# untitled.net
KiCad netlist of a schematic drawn in EAGLE
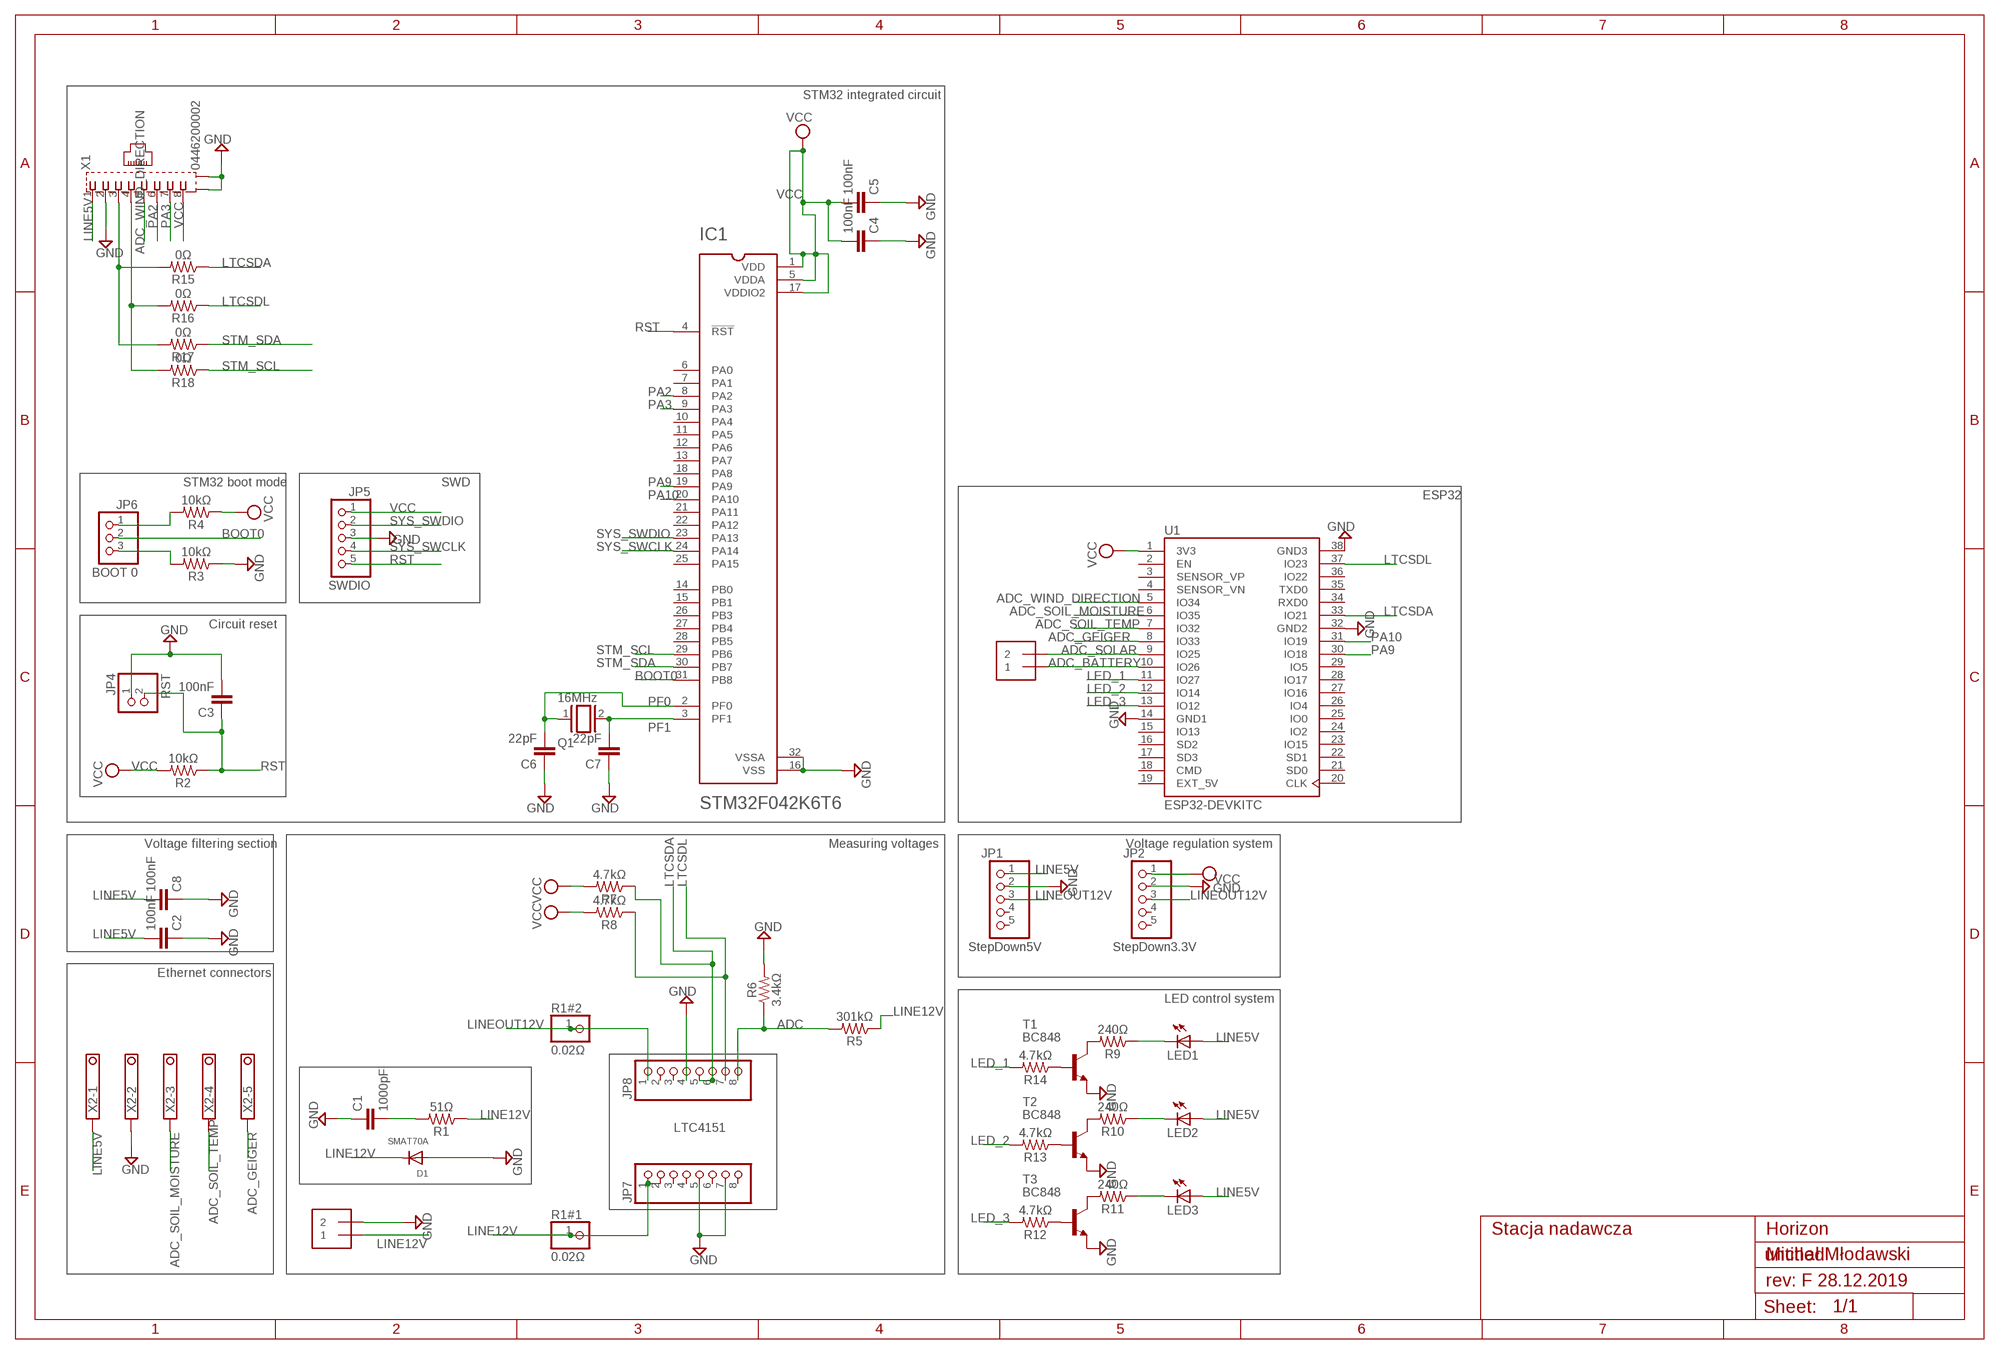
[diagram p0: schematic, sheet 1]

(export (version "E")
  (design (tool "Eeschema 10.0.6"))
  (components
    (comp (ref "C1")
      (value "1000pF")
      (footprint "eagle-import:1206")
      (libsource (lib "eagle-import") (part "10UF-1206-6.3V-20%"))
    )
    (comp (ref "C2")
      (value "100nF")
      (footprint "eagle-import:1206")
      (libsource (lib "eagle-import") (part "10UF-1206-6.3V-20%"))
    )
    (comp (ref "C3")
      (value "100nF")
      (footprint "eagle-import:1206")
      (libsource (lib "eagle-import") (part "10UF-1206-6.3V-20%"))
    )
    (comp (ref "C4")
      (value "100nF")
      (footprint "eagle-import:1206")
      (libsource (lib "eagle-import") (part "10UF-1206-6.3V-20%"))
    )
    (comp (ref "C5")
      (value "100nF")
      (footprint "eagle-import:1206")
      (libsource (lib "eagle-import") (part "10UF-1206-6.3V-20%"))
    )
    (comp (ref "C6")
      (value "22pF")
      (footprint "eagle-import:1206")
      (libsource (lib "eagle-import") (part "10UF-1206-6.3V-20%"))
    )
    (comp (ref "C7")
      (value "22pF")
      (footprint "eagle-import:1206")
      (libsource (lib "eagle-import") (part "10UF-1206-6.3V-20%"))
    )
    (comp (ref "C8")
      (value "100nF")
      (footprint "eagle-import:1206")
      (libsource (lib "eagle-import") (part "10UF-1206-6.3V-20%"))
    )
    (comp (ref "D1")
      (value "SMAT70A")
      (footprint "eagle-import:SMADIODE")
      (libsource (lib "eagle-import") (part "DIODESMA"))
    )
    (comp (ref "IC1")
      (value "STM32F042K6T6")
      (footprint "eagle-import:QFP80P900X900X160-32N")
      (fields (field (name "MF") "STMicroelectronics"))
      (libsource (lib "eagle-import") (part "STM32F042K6T6"))
    )
    (comp (ref "J1")
      (value "1X2-3.5MM")
      (footprint "eagle-import:1X2-3.5MM")
      (libsource (lib "eagle-import") (part "1X2-3.5MM"))
    )
    (comp (ref "J2")
      (value "1X2-3.5MM")
      (footprint "eagle-import:1X2-3.5MM")
      (libsource (lib "eagle-import") (part "1X2-3.5MM"))
    )
    (comp (ref "JP1")
      (value "StepDown5V")
      (footprint "eagle-import:1X05")
      (libsource (lib "eagle-import") (part "PINHD-1X5"))
    )
    (comp (ref "JP2")
      (value "StepDown3.3V")
      (footprint "eagle-import:1X05")
      (libsource (lib "eagle-import") (part "PINHD-1X5"))
    )
    (comp (ref "JP4")
      (value "RST")
      (footprint "eagle-import:1X02")
      (libsource (lib "eagle-import") (part "PINHD-1X2"))
    )
    (comp (ref "JP5")
      (value "SWDIO")
      (footprint "eagle-import:1X05")
      (libsource (lib "eagle-import") (part "PINHD-1X5"))
    )
    (comp (ref "JP6")
      (value "BOOT 0")
      (footprint "eagle-import:1X03")
      (libsource (lib "eagle-import") (part "PINHD-1X3"))
    )
    (comp (ref "JP7")
      (value "PINHD-1X8")
      (footprint "eagle-import:1X08")
      (libsource (lib "eagle-import") (part "PINHD-1X8"))
    )
    (comp (ref "JP8")
      (value "PINHD-1X8")
      (footprint "eagle-import:1X08")
      (libsource (lib "eagle-import") (part "PINHD-1X8"))
    )
    (comp (ref "LED1")
      (value "LED5MM")
      (footprint "eagle-import:LED5MM")
      (libsource (lib "eagle-import") (part "LED5MM"))
    )
    (comp (ref "LED2")
      (value "LED5MM")
      (footprint "eagle-import:LED5MM")
      (libsource (lib "eagle-import") (part "LED5MM"))
    )
    (comp (ref "LED3")
      (value "LED5MM")
      (footprint "eagle-import:LED5MM")
      (libsource (lib "eagle-import") (part "LED5MM"))
    )
    (comp (ref "Q1")
      (value "16MHz")
      (footprint "eagle-import:QS")
      (libsource (lib "eagle-import") (part "XTAL/S"))
    )
    (comp (ref "R1")
      (value "51Ω")
      (footprint "eagle-import:1206")
      (libsource (lib "eagle-import") (part "RESISTOR1206"))
    )
    (comp (ref "R1#1")
      (value "0.02Ω")
      (footprint "eagle-import:1X01")
      (libsource (lib "eagle-import") (part "PINHD-1X1"))
    )
    (comp (ref "R1#2")
      (value "0.02Ω")
      (footprint "eagle-import:1X01")
      (libsource (lib "eagle-import") (part "PINHD-1X1"))
    )
    (comp (ref "R2")
      (value "10kΩ")
      (footprint "eagle-import:1206")
      (libsource (lib "eagle-import") (part "RESISTOR1206"))
    )
    (comp (ref "R3")
      (value "10kΩ")
      (footprint "eagle-import:1206")
      (libsource (lib "eagle-import") (part "RESISTOR1206"))
    )
    (comp (ref "R4")
      (value "10kΩ")
      (footprint "eagle-import:1206")
      (libsource (lib "eagle-import") (part "RESISTOR1206"))
    )
    (comp (ref "R5")
      (value "301kΩ")
      (footprint "eagle-import:1206")
      (libsource (lib "eagle-import") (part "RESISTOR1206"))
    )
    (comp (ref "R6")
      (value "3.4kΩ")
      (footprint "eagle-import:1206")
      (libsource (lib "eagle-import") (part "RESISTOR1206"))
    )
    (comp (ref "R7")
      (value "4.7kΩ")
      (footprint "eagle-import:1206")
      (libsource (lib "eagle-import") (part "RESISTOR1206"))
    )
    (comp (ref "R8")
      (value "4.7kΩ")
      (footprint "eagle-import:1206")
      (libsource (lib "eagle-import") (part "RESISTOR1206"))
    )
    (comp (ref "R9")
      (value "240Ω")
      (footprint "eagle-import:1206")
      (libsource (lib "eagle-import") (part "RESISTOR1206"))
    )
    (comp (ref "R10")
      (value "240Ω")
      (footprint "eagle-import:1206")
      (libsource (lib "eagle-import") (part "RESISTOR1206"))
    )
    (comp (ref "R11")
      (value "240Ω")
      (footprint "eagle-import:1206")
      (libsource (lib "eagle-import") (part "RESISTOR1206"))
    )
    (comp (ref "R12")
      (value "4.7kΩ")
      (footprint "eagle-import:1206")
      (libsource (lib "eagle-import") (part "RESISTOR1206"))
    )
    (comp (ref "R13")
      (value "4.7kΩ")
      (footprint "eagle-import:1206")
      (libsource (lib "eagle-import") (part "RESISTOR1206"))
    )
    (comp (ref "R14")
      (value "4.7kΩ")
      (footprint "eagle-import:1206")
      (libsource (lib "eagle-import") (part "RESISTOR1206"))
    )
    (comp (ref "R15")
      (value "0Ω")
      (footprint "eagle-import:1206")
      (libsource (lib "eagle-import") (part "RESISTOR1206"))
    )
    (comp (ref "R16")
      (value "0Ω")
      (footprint "eagle-import:1206")
      (libsource (lib "eagle-import") (part "RESISTOR1206"))
    )
    (comp (ref "R17")
      (value "0Ω")
      (footprint "eagle-import:1206")
      (libsource (lib "eagle-import") (part "RESISTOR1206"))
    )
    (comp (ref "R18")
      (value "0Ω")
      (footprint "eagle-import:1206")
      (libsource (lib "eagle-import") (part "RESISTOR1206"))
    )
    (comp (ref "T1")
      (value "BC848")
      (footprint "eagle-import:SOT23")
      (libsource (lib "eagle-import") (part "BC848"))
    )
    (comp (ref "T2")
      (value "BC848")
      (footprint "eagle-import:SOT23")
      (libsource (lib "eagle-import") (part "BC848"))
    )
    (comp (ref "T3")
      (value "BC848")
      (footprint "eagle-import:SOT23")
      (libsource (lib "eagle-import") (part "BC848"))
    )
    (comp (ref "U1")
      (value "ESP32-DEVKITC")
      (footprint "eagle-import:MODULE_ESP32-DEVKITC")
      (fields (field (name "MF") "Espressif Systems") (field (name "MP") "ESP32-DEVKITC-32D-F"))
      (libsource (lib "eagle-import") (part "ESP32-DEVKITC"))
    )
    (comp (ref "X1")
      (value "0446200002")
      (footprint "eagle-import:0446200002")
      (fields (field (name "MF") "MOLEX"))
      (libsource (lib "eagle-import") (part "0446200002"))
    )
    (comp (ref "X2")
      (value "TERMINAL-BLOCK-3.5MM-5-PIN-LONG-PAD")
      (footprint "eagle-import:TERMINAL-BLOCK-5-PIN-3.5MM-LONG-PAD")
      (libsource (lib "eagle-import") (part "TERMINAL-BLOCK-3.5MM-5-PIN-LONG-PAD"))
    )
  )
  (nets
    (net (code "1") (name "/ADC") (class "Default")
      (node (ref "JP8") (pin "8") (pinfunction "8_8") (pintype "passive"))
      (node (ref "R5") (pin "2") (pinfunction "2_2") (pintype "passive"))
      (node (ref "R6") (pin "1") (pinfunction "1_1") (pintype "passive"))
    )
    (net (code "2") (name "/ADC_BATTERY") (class "Default")
      (node (ref "J1") (pin "1") (pinfunction "1_1") (pintype "passive"))
      (node (ref "U1") (pin "10") (pinfunction "IO26_10") (pintype "bidirectional"))
    )
    (net (code "3") (name "/ADC_GEIGER") (class "Default")
      (node (ref "U1") (pin "8") (pinfunction "IO33_8") (pintype "bidirectional"))
      (node (ref "X2") (pin "5") (pinfunction "K_5") (pintype "passive"))
    )
    (net (code "4") (name "/ADC_SOIL_MOISTURE") (class "Default")
      (node (ref "U1") (pin "6") (pinfunction "IO35_6") (pintype "bidirectional"))
      (node (ref "X2") (pin "3") (pinfunction "K_3") (pintype "passive"))
    )
    (net (code "5") (name "/ADC_SOIL_TEMP") (class "Default")
      (node (ref "U1") (pin "7") (pinfunction "IO32_7") (pintype "bidirectional"))
      (node (ref "X2") (pin "4") (pinfunction "K_4") (pintype "passive"))
    )
    (net (code "6") (name "/ADC_SOLAR") (class "Default")
      (node (ref "J1") (pin "2") (pinfunction "2_2") (pintype "passive"))
      (node (ref "U1") (pin "9") (pinfunction "IO25_9") (pintype "bidirectional"))
    )
    (net (code "7") (name "/ADC_WIND_DIRECTION") (class "Default")
      (node (ref "U1") (pin "5") (pinfunction "IO34_5") (pintype "bidirectional"))
      (node (ref "X1") (pin "5") (pinfunction "5_5") (pintype "passive"))
    )
    (net (code "8") (name "/BOOT0") (class "Default")
      (node (ref "IC1") (pin "31") (pinfunction "PB8_31") (pintype "bidirectional"))
      (node (ref "JP6") (pin "2") (pinfunction "2_2") (pintype "passive"))
    )
    (net (code "9") (name "/EXT_5V") (class "Default")
      (node (ref "U1") (pin "19") (pinfunction "EXT_5V_19") (pintype "power_in"))
    )
    (net (code "10") (name "/LED_1") (class "Default")
      (node (ref "R14") (pin "2") (pinfunction "2_2") (pintype "passive"))
      (node (ref "U1") (pin "11") (pinfunction "IO27_11") (pintype "bidirectional"))
    )
    (net (code "11") (name "/LED_2") (class "Default")
      (node (ref "R13") (pin "2") (pinfunction "2_2") (pintype "passive"))
      (node (ref "U1") (pin "12") (pinfunction "IO14_12") (pintype "bidirectional"))
    )
    (net (code "12") (name "/LED_3") (class "Default")
      (node (ref "R12") (pin "2") (pinfunction "2_2") (pintype "passive"))
      (node (ref "U1") (pin "13") (pinfunction "IO12_13") (pintype "bidirectional"))
    )
    (net (code "13") (name "/LINE5V") (class "Default")
      (node (ref "C2") (pin "2") (pinfunction "2_2") (pintype "passive"))
      (node (ref "C8") (pin "2") (pinfunction "2_2") (pintype "passive"))
      (node (ref "JP1") (pin "1") (pinfunction "1_1") (pintype "passive"))
      (node (ref "LED1") (pin "A") (pinfunction "A_A") (pintype "passive"))
      (node (ref "LED2") (pin "A") (pinfunction "A_A") (pintype "passive"))
      (node (ref "LED3") (pin "A") (pinfunction "A_A") (pintype "passive"))
      (node (ref "X1") (pin "1") (pinfunction "1_1") (pintype "passive"))
      (node (ref "X2") (pin "1") (pinfunction "K_1") (pintype "passive"))
    )
    (net (code "14") (name "/LINE12V") (class "Default")
      (node (ref "D1") (pin "C") (pinfunction "C_C") (pintype "passive"))
      (node (ref "J2") (pin "1") (pinfunction "1_1") (pintype "passive"))
      (node (ref "JP7") (pin "1") (pinfunction "1_1") (pintype "passive"))
      (node (ref "JP7") (pin "2") (pinfunction "2_2") (pintype "passive"))
      (node (ref "R1") (pin "1") (pinfunction "1_1") (pintype "passive"))
      (node (ref "R1#1") (pin "1") (pinfunction "1_1") (pintype "passive"))
      (node (ref "R5") (pin "1") (pinfunction "1_1") (pintype "passive"))
    )
    (net (code "15") (name "/LINEOUT12V") (class "Default")
      (node (ref "JP1") (pin "3") (pinfunction "3_3") (pintype "passive"))
      (node (ref "JP2") (pin "3") (pinfunction "3_3") (pintype "passive"))
      (node (ref "JP8") (pin "1") (pinfunction "1_1") (pintype "passive"))
      (node (ref "R1#2") (pin "1") (pinfunction "1_1") (pintype "passive"))
    )
    (net (code "16") (name "/LTCSDA") (class "Default")
      (node (ref "JP8") (pin "5") (pinfunction "5_5") (pintype "passive"))
      (node (ref "JP8") (pin "6") (pinfunction "6_6") (pintype "passive"))
      (node (ref "R15") (pin "1") (pinfunction "1_1") (pintype "passive"))
      (node (ref "R7") (pin "1") (pinfunction "1_1") (pintype "passive"))
      (node (ref "U1") (pin "33") (pinfunction "IO21_33") (pintype "bidirectional"))
    )
    (net (code "17") (name "/LTCSDL") (class "Default")
      (node (ref "JP8") (pin "7") (pinfunction "7_7") (pintype "passive"))
      (node (ref "R16") (pin "1") (pinfunction "1_1") (pintype "passive"))
      (node (ref "R8") (pin "1") (pinfunction "1_1") (pintype "passive"))
      (node (ref "U1") (pin "37") (pinfunction "IO23_37") (pintype "bidirectional"))
    )
    (net (code "18") (name "/PA2") (class "Default")
      (node (ref "IC1") (pin "8") (pinfunction "PA2_8") (pintype "bidirectional"))
      (node (ref "X1") (pin "6") (pinfunction "6_6") (pintype "passive"))
    )
    (net (code "19") (name "/PA3") (class "Default")
      (node (ref "IC1") (pin "9") (pinfunction "PA3_9") (pintype "bidirectional"))
      (node (ref "X1") (pin "7") (pinfunction "7_7") (pintype "passive"))
    )
    (net (code "20") (name "/PA9") (class "Default")
      (node (ref "IC1") (pin "19") (pinfunction "PA9_19") (pintype "bidirectional"))
      (node (ref "U1") (pin "30") (pinfunction "IO18_30") (pintype "bidirectional"))
    )
    (net (code "21") (name "/PA10") (class "Default")
      (node (ref "IC1") (pin "20") (pinfunction "PA10_20") (pintype "bidirectional"))
      (node (ref "U1") (pin "31") (pinfunction "IO19_31") (pintype "bidirectional"))
    )
    (net (code "22") (name "/PF0") (class "Default")
      (node (ref "C6") (pin "2") (pinfunction "2_2") (pintype "passive"))
      (node (ref "IC1") (pin "2") (pinfunction "PF0_2") (pintype "bidirectional"))
      (node (ref "Q1") (pin "1") (pinfunction "1_1") (pintype "passive"))
    )
    (net (code "23") (name "/PF1") (class "Default")
      (node (ref "C7") (pin "2") (pinfunction "2_2") (pintype "passive"))
      (node (ref "IC1") (pin "3") (pinfunction "PF1_3") (pintype "bidirectional"))
      (node (ref "Q1") (pin "2") (pinfunction "2_2") (pintype "passive"))
    )
    (net (code "24") (name "/RST") (class "Default")
      (node (ref "C3") (pin "1") (pinfunction "1_1") (pintype "passive"))
      (node (ref "IC1") (pin "4") (pinfunction "~{RST}_4") (pintype "input"))
      (node (ref "JP4") (pin "2") (pinfunction "2_2") (pintype "passive"))
      (node (ref "JP5") (pin "5") (pinfunction "5_5") (pintype "passive"))
      (node (ref "R2") (pin "1") (pinfunction "1_1") (pintype "passive"))
    )
    (net (code "25") (name "/STM_SCL") (class "Default")
      (node (ref "IC1") (pin "29") (pinfunction "PB6_29") (pintype "bidirectional"))
      (node (ref "R18") (pin "1") (pinfunction "1_1") (pintype "passive"))
    )
    (net (code "26") (name "/STM_SDA") (class "Default")
      (node (ref "IC1") (pin "30") (pinfunction "PB7_30") (pintype "bidirectional"))
      (node (ref "R17") (pin "1") (pinfunction "1_1") (pintype "passive"))
    )
    (net (code "27") (name "/SYS_SWCLK") (class "Default")
      (node (ref "IC1") (pin "24") (pinfunction "PA14_24") (pintype "bidirectional"))
      (node (ref "JP5") (pin "4") (pinfunction "4_4") (pintype "passive"))
    )
    (net (code "28") (name "/SYS_SWDIO") (class "Default")
      (node (ref "IC1") (pin "23") (pinfunction "PA13_23") (pintype "bidirectional"))
      (node (ref "JP5") (pin "2") (pinfunction "2_2") (pintype "passive"))
    )
    (net (code "29") (name "GND") (class "Default")
      (node (ref "C1") (pin "1") (pinfunction "1_1") (pintype "passive"))
      (node (ref "C2") (pin "1") (pinfunction "1_1") (pintype "passive"))
      (node (ref "C3") (pin "2") (pinfunction "2_2") (pintype "passive"))
      (node (ref "C4") (pin "1") (pinfunction "1_1") (pintype "passive"))
      (node (ref "C5") (pin "1") (pinfunction "1_1") (pintype "passive"))
      (node (ref "C6") (pin "1") (pinfunction "1_1") (pintype "passive"))
      (node (ref "C7") (pin "1") (pinfunction "1_1") (pintype "passive"))
      (node (ref "C8") (pin "1") (pinfunction "1_1") (pintype "passive"))
      (node (ref "D1") (pin "A") (pinfunction "A_A") (pintype "passive"))
      (node (ref "IC1") (pin "16") (pinfunction "VSS_16") (pintype "passive"))
      (node (ref "IC1") (pin "32") (pinfunction "VSSA_32") (pintype "passive"))
      (node (ref "J2") (pin "2") (pinfunction "2_2") (pintype "passive"))
      (node (ref "JP1") (pin "2") (pinfunction "2_2") (pintype "passive"))
      (node (ref "JP2") (pin "2") (pinfunction "2_2") (pintype "passive"))
      (node (ref "JP4") (pin "1") (pinfunction "1_1") (pintype "passive"))
      (node (ref "JP5") (pin "3") (pinfunction "3_3") (pintype "passive"))
      (node (ref "JP7") (pin "5") (pinfunction "5_5") (pintype "passive"))
      (node (ref "JP7") (pin "7") (pinfunction "7_7") (pintype "passive"))
      (node (ref "JP8") (pin "4") (pinfunction "4_4") (pintype "passive"))
      (node (ref "R3") (pin "1") (pinfunction "1_1") (pintype "passive"))
      (node (ref "R6") (pin "2") (pinfunction "2_2") (pintype "passive"))
      (node (ref "T1") (pin "2") (pinfunction "E_2") (pintype "passive"))
      (node (ref "T2") (pin "2") (pinfunction "E_2") (pintype "passive"))
      (node (ref "T3") (pin "2") (pinfunction "E_2") (pintype "passive"))
      (node (ref "U1") (pin "14") (pinfunction "GND1_14") (pintype "power_in"))
      (node (ref "U1") (pin "32") (pinfunction "GND2_32") (pintype "power_in"))
      (node (ref "U1") (pin "38") (pinfunction "GND3_38") (pintype "power_in"))
      (node (ref "X1") (pin "2") (pinfunction "2_2") (pintype "passive"))
      (node (ref "X1") (pin "S@1") (pinfunction "S1_S@1") (pintype "passive"))
      (node (ref "X1") (pin "S@2") (pinfunction "S2_S@2") (pintype "passive"))
      (node (ref "X2") (pin "2") (pinfunction "K_2") (pintype "passive"))
    )
    (net (code "30") (name "Net-(C1-Pad2)") (class "Default")
      (node (ref "C1") (pin "2") (pinfunction "2_2") (pintype "passive"))
      (node (ref "R1") (pin "2") (pinfunction "2_2") (pintype "passive"))
    )
    (net (code "31") (name "Net-(JP6-Pad1)") (class "Default")
      (node (ref "JP6") (pin "1") (pinfunction "1_1") (pintype "passive"))
      (node (ref "R4") (pin "2") (pinfunction "2_2") (pintype "passive"))
    )
    (net (code "32") (name "Net-(JP6-Pad3)") (class "Default")
      (node (ref "JP6") (pin "3") (pinfunction "3_3") (pintype "passive"))
      (node (ref "R3") (pin "2") (pinfunction "2_2") (pintype "passive"))
    )
    (net (code "33") (name "Net-(LED1-C)") (class "Default")
      (node (ref "LED1") (pin "K") (pinfunction "C_K") (pintype "passive"))
      (node (ref "R9") (pin "1") (pinfunction "1_1") (pintype "passive"))
    )
    (net (code "34") (name "Net-(LED2-C)") (class "Default")
      (node (ref "LED2") (pin "K") (pinfunction "C_K") (pintype "passive"))
      (node (ref "R10") (pin "1") (pinfunction "1_1") (pintype "passive"))
    )
    (net (code "35") (name "Net-(LED3-C)") (class "Default")
      (node (ref "LED3") (pin "K") (pinfunction "C_K") (pintype "passive"))
      (node (ref "R11") (pin "1") (pinfunction "1_1") (pintype "passive"))
    )
    (net (code "36") (name "Net-(R15-Pad2)") (class "Default")
      (node (ref "R15") (pin "2") (pinfunction "2_2") (pintype "passive"))
      (node (ref "R17") (pin "2") (pinfunction "2_2") (pintype "passive"))
      (node (ref "X1") (pin "3") (pinfunction "3_3") (pintype "passive"))
    )
    (net (code "37") (name "Net-(R16-Pad2)") (class "Default")
      (node (ref "R16") (pin "2") (pinfunction "2_2") (pintype "passive"))
      (node (ref "R18") (pin "2") (pinfunction "2_2") (pintype "passive"))
      (node (ref "X1") (pin "4") (pinfunction "4_4") (pintype "passive"))
    )
    (net (code "38") (name "Net-(T1-B)") (class "Default")
      (node (ref "R14") (pin "1") (pinfunction "1_1") (pintype "passive"))
      (node (ref "T1") (pin "1") (pinfunction "B_1") (pintype "passive"))
    )
    (net (code "39") (name "Net-(T1-C)") (class "Default")
      (node (ref "R9") (pin "2") (pinfunction "2_2") (pintype "passive"))
      (node (ref "T1") (pin "3") (pinfunction "C_3") (pintype "passive"))
    )
    (net (code "40") (name "Net-(T2-B)") (class "Default")
      (node (ref "R13") (pin "1") (pinfunction "1_1") (pintype "passive"))
      (node (ref "T2") (pin "1") (pinfunction "B_1") (pintype "passive"))
    )
    (net (code "41") (name "Net-(T2-C)") (class "Default")
      (node (ref "R10") (pin "2") (pinfunction "2_2") (pintype "passive"))
      (node (ref "T2") (pin "3") (pinfunction "C_3") (pintype "passive"))
    )
    (net (code "42") (name "Net-(T3-B)") (class "Default")
      (node (ref "R12") (pin "1") (pinfunction "1_1") (pintype "passive"))
      (node (ref "T3") (pin "1") (pinfunction "B_1") (pintype "passive"))
    )
    (net (code "43") (name "Net-(T3-C)") (class "Default")
      (node (ref "R11") (pin "2") (pinfunction "2_2") (pintype "passive"))
      (node (ref "T3") (pin "3") (pinfunction "C_3") (pintype "passive"))
    )
    (net (code "44") (name "VCC") (class "Default")
      (node (ref "C4") (pin "2") (pinfunction "2_2") (pintype "passive"))
      (node (ref "C5") (pin "2") (pinfunction "2_2") (pintype "passive"))
      (node (ref "IC1") (pin "1") (pinfunction "VDD_1") (pintype "power_in"))
      (node (ref "IC1") (pin "17") (pinfunction "VDDIO2_17") (pintype "power_in"))
      (node (ref "IC1") (pin "5") (pinfunction "VDDA_5") (pintype "power_in"))
      (node (ref "JP2") (pin "1") (pinfunction "1_1") (pintype "passive"))
      (node (ref "JP5") (pin "1") (pinfunction "1_1") (pintype "passive"))
      (node (ref "R2") (pin "2") (pinfunction "2_2") (pintype "passive"))
      (node (ref "R4") (pin "1") (pinfunction "1_1") (pintype "passive"))
      (node (ref "R7") (pin "2") (pinfunction "2_2") (pintype "passive"))
      (node (ref "R8") (pin "2") (pinfunction "2_2") (pintype "passive"))
      (node (ref "U1") (pin "1") (pinfunction "3V3_1") (pintype "power_in"))
      (node (ref "X1") (pin "8") (pinfunction "8_8") (pintype "passive"))
    )
    (net (code "45") (name "unconnected-(IC1-PA0-Pad6)") (class "Default")
      (node (ref "IC1") (pin "6") (pinfunction "PA0_6") (pintype "bidirectional"))
    )
    (net (code "46") (name "unconnected-(IC1-PA1-Pad7)") (class "Default")
      (node (ref "IC1") (pin "7") (pinfunction "PA1_7") (pintype "bidirectional"))
    )
    (net (code "47") (name "unconnected-(IC1-PA4-Pad10)") (class "Default")
      (node (ref "IC1") (pin "10") (pinfunction "PA4_10") (pintype "bidirectional"))
    )
    (net (code "48") (name "unconnected-(IC1-PA5-Pad11)") (class "Default")
      (node (ref "IC1") (pin "11") (pinfunction "PA5_11") (pintype "bidirectional"))
    )
    (net (code "49") (name "unconnected-(IC1-PA6-Pad12)") (class "Default")
      (node (ref "IC1") (pin "12") (pinfunction "PA6_12") (pintype "bidirectional"))
    )
    (net (code "50") (name "unconnected-(IC1-PA7-Pad13)") (class "Default")
      (node (ref "IC1") (pin "13") (pinfunction "PA7_13") (pintype "bidirectional"))
    )
    (net (code "51") (name "unconnected-(IC1-PA8-Pad18)") (class "Default")
      (node (ref "IC1") (pin "18") (pinfunction "PA8_18") (pintype "bidirectional"))
    )
    (net (code "52") (name "unconnected-(IC1-PA11-Pad21)") (class "Default")
      (node (ref "IC1") (pin "21") (pinfunction "PA11_21") (pintype "bidirectional"))
    )
    (net (code "53") (name "unconnected-(IC1-PA12-Pad22)") (class "Default")
      (node (ref "IC1") (pin "22") (pinfunction "PA12_22") (pintype "bidirectional"))
    )
    (net (code "54") (name "unconnected-(IC1-PA15-Pad25)") (class "Default")
      (node (ref "IC1") (pin "25") (pinfunction "PA15_25") (pintype "bidirectional"))
    )
    (net (code "55") (name "unconnected-(IC1-PB0-Pad14)") (class "Default")
      (node (ref "IC1") (pin "14") (pinfunction "PB0_14") (pintype "bidirectional"))
    )
    (net (code "56") (name "unconnected-(IC1-PB1-Pad15)") (class "Default")
      (node (ref "IC1") (pin "15") (pinfunction "PB1_15") (pintype "bidirectional"))
    )
    (net (code "57") (name "unconnected-(IC1-PB3-Pad26)") (class "Default")
      (node (ref "IC1") (pin "26") (pinfunction "PB3_26") (pintype "bidirectional"))
    )
    (net (code "58") (name "unconnected-(IC1-PB4-Pad27)") (class "Default")
      (node (ref "IC1") (pin "27") (pinfunction "PB4_27") (pintype "bidirectional"))
    )
    (net (code "59") (name "unconnected-(IC1-PB5-Pad28)") (class "Default")
      (node (ref "IC1") (pin "28") (pinfunction "PB5_28") (pintype "bidirectional"))
    )
    (net (code "60") (name "unconnected-(JP1-Pad4)") (class "Default")
      (node (ref "JP1") (pin "4") (pinfunction "4_4") (pintype "passive"))
    )
    (net (code "61") (name "unconnected-(JP1-Pad5)") (class "Default")
      (node (ref "JP1") (pin "5") (pinfunction "5_5") (pintype "passive"))
    )
    (net (code "62") (name "unconnected-(JP2-Pad4)") (class "Default")
      (node (ref "JP2") (pin "4") (pinfunction "4_4") (pintype "passive"))
    )
    (net (code "63") (name "unconnected-(JP2-Pad5)") (class "Default")
      (node (ref "JP2") (pin "5") (pinfunction "5_5") (pintype "passive"))
    )
    (net (code "64") (name "unconnected-(JP7-Pad3)") (class "Default")
      (node (ref "JP7") (pin "3") (pinfunction "3_3") (pintype "passive"))
    )
    (net (code "65") (name "unconnected-(JP7-Pad4)") (class "Default")
      (node (ref "JP7") (pin "4") (pinfunction "4_4") (pintype "passive"))
    )
    (net (code "66") (name "unconnected-(JP7-Pad6)") (class "Default")
      (node (ref "JP7") (pin "6") (pinfunction "6_6") (pintype "passive"))
    )
    (net (code "67") (name "unconnected-(JP7-Pad8)") (class "Default")
      (node (ref "JP7") (pin "8") (pinfunction "8_8") (pintype "passive"))
    )
    (net (code "68") (name "unconnected-(JP8-Pad2)") (class "Default")
      (node (ref "JP8") (pin "2") (pinfunction "2_2") (pintype "passive"))
    )
    (net (code "69") (name "unconnected-(JP8-Pad3)") (class "Default")
      (node (ref "JP8") (pin "3") (pinfunction "3_3") (pintype "passive"))
    )
    (net (code "70") (name "unconnected-(U1-CLK-Pad20)") (class "Default")
      (node (ref "U1") (pin "20") (pinfunction "CLK_20") (pintype "input"))
    )
    (net (code "71") (name "unconnected-(U1-CMD-Pad18)") (class "Default")
      (node (ref "U1") (pin "18") (pinfunction "CMD_18") (pintype "bidirectional"))
    )
    (net (code "72") (name "unconnected-(U1-EN-Pad2)") (class "Default")
      (node (ref "U1") (pin "2") (pinfunction "EN_2") (pintype "input"))
    )
    (net (code "73") (name "unconnected-(U1-IO0-Pad25)") (class "Default")
      (node (ref "U1") (pin "25") (pinfunction "IO0_25") (pintype "bidirectional"))
    )
    (net (code "74") (name "unconnected-(U1-IO2-Pad24)") (class "Default")
      (node (ref "U1") (pin "24") (pinfunction "IO2_24") (pintype "bidirectional"))
    )
    (net (code "75") (name "unconnected-(U1-IO4-Pad26)") (class "Default")
      (node (ref "U1") (pin "26") (pinfunction "IO4_26") (pintype "bidirectional"))
    )
    (net (code "76") (name "unconnected-(U1-IO5-Pad29)") (class "Default")
      (node (ref "U1") (pin "29") (pinfunction "IO5_29") (pintype "bidirectional"))
    )
    (net (code "77") (name "unconnected-(U1-IO13-Pad15)") (class "Default")
      (node (ref "U1") (pin "15") (pinfunction "IO13_15") (pintype "bidirectional"))
    )
    (net (code "78") (name "unconnected-(U1-IO15-Pad23)") (class "Default")
      (node (ref "U1") (pin "23") (pinfunction "IO15_23") (pintype "bidirectional"))
    )
    (net (code "79") (name "unconnected-(U1-IO16-Pad27)") (class "Default")
      (node (ref "U1") (pin "27") (pinfunction "IO16_27") (pintype "bidirectional"))
    )
    (net (code "80") (name "unconnected-(U1-IO17-Pad28)") (class "Default")
      (node (ref "U1") (pin "28") (pinfunction "IO17_28") (pintype "bidirectional"))
    )
    (net (code "81") (name "unconnected-(U1-IO22-Pad36)") (class "Default")
      (node (ref "U1") (pin "36") (pinfunction "IO22_36") (pintype "bidirectional"))
    )
    (net (code "82") (name "unconnected-(U1-RXD0-Pad34)") (class "Default")
      (node (ref "U1") (pin "34") (pinfunction "RXD0_34") (pintype "input"))
    )
    (net (code "83") (name "unconnected-(U1-SD0-Pad21)") (class "Default")
      (node (ref "U1") (pin "21") (pinfunction "SD0_21") (pintype "bidirectional"))
    )
    (net (code "84") (name "unconnected-(U1-SD1-Pad22)") (class "Default")
      (node (ref "U1") (pin "22") (pinfunction "SD1_22") (pintype "bidirectional"))
    )
    (net (code "85") (name "unconnected-(U1-SD2-Pad16)") (class "Default")
      (node (ref "U1") (pin "16") (pinfunction "SD2_16") (pintype "bidirectional"))
    )
    (net (code "86") (name "unconnected-(U1-SD3-Pad17)") (class "Default")
      (node (ref "U1") (pin "17") (pinfunction "SD3_17") (pintype "bidirectional"))
    )
    (net (code "87") (name "unconnected-(U1-SENSOR_VN-Pad4)") (class "Default")
      (node (ref "U1") (pin "4") (pinfunction "SENSOR_VN_4") (pintype "input"))
    )
    (net (code "88") (name "unconnected-(U1-SENSOR_VP-Pad3)") (class "Default")
      (node (ref "U1") (pin "3") (pinfunction "SENSOR_VP_3") (pintype "input"))
    )
    (net (code "89") (name "unconnected-(U1-TXD0-Pad35)") (class "Default")
      (node (ref "U1") (pin "35") (pinfunction "TXD0_35") (pintype "output"))
    )
  )
)
